# Gate_Driver.net
KiCad netlist of a schematic drawn in Altium Designer
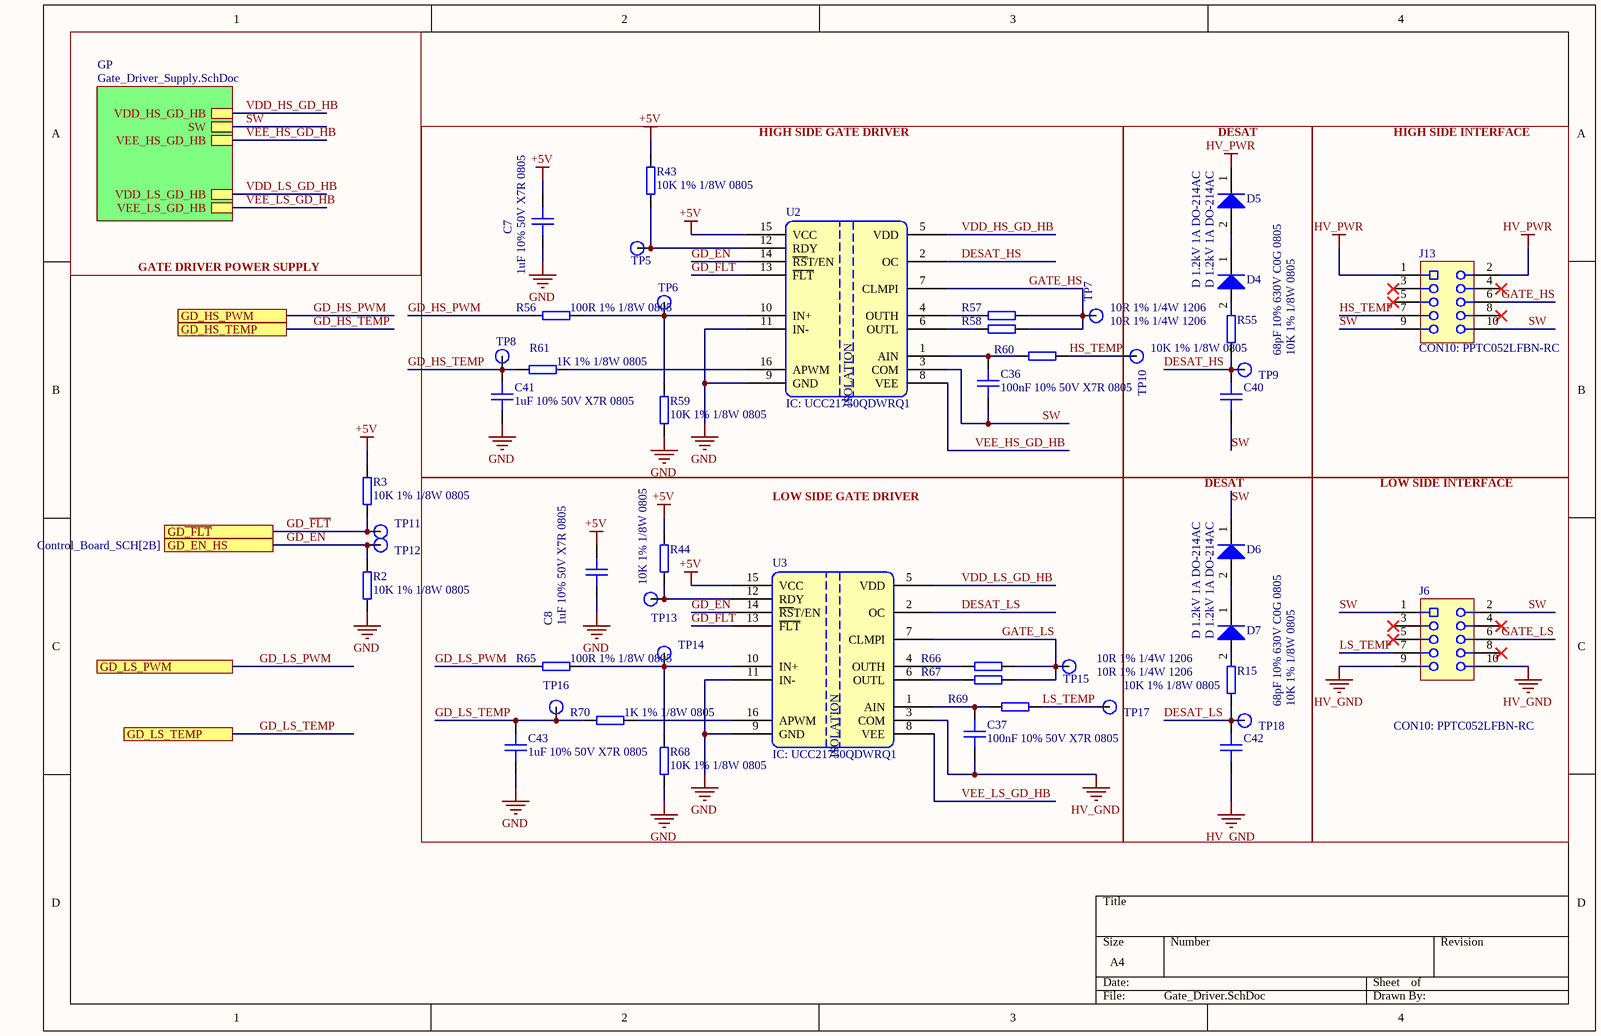
[diagram p0: Gate_Driver.SchDoc]

(export (version "E")
  (design (tool "Eeschema 10.0.6"))
  (components
    (comp (ref "C7")
      (value "1uF 10% 50V X7R 0805")
      (footprint "CAPC2012X10N")
      (fields
        (field (name "MANUFACTURER PART NUMBER") "C2012X7R1H105K125AB")
        (field (name "MANUFACTURER") "TDK")
      )
      (libsource (lib "EMEA- E-Tech Racing- I'Escola d'Enginyeria de Barcelona Est") (part "68pF 10 630V C0G 0805"))
    )
    (comp (ref "C8")
      (value "1uF 10% 50V X7R 0805")
      (footprint "CAPC2012X10N")
      (fields
        (field (name "MANUFACTURER PART NUMBER") "C2012X7R1H105K125AB")
        (field (name "MANUFACTURER") "TDK")
      )
      (libsource (lib "EMEA- E-Tech Racing- I'Escola d'Enginyeria de Barcelona Est") (part "68pF 10 630V C0G 0805"))
    )
    (comp (ref "C36")
      (value "100nF 10% 50V X7R 0805")
      (footprint "CAPC2012X10N")
      (description "Multilayer Ceramic Capacitors MLCC - SMD/SMT 50V 0.1uF X7R 0805 10%")
      (fields
        (field (name "MANUFACTURER") "Stackpole Electronics")
        (field (name "MANUFACTURER PART NUMBER") "CML0805X7R104KT50V")
      )
      (libsource (lib "EMEA- E-Tech Racing- I'Escola d'Enginyeria de Barcelona Est") (part "100nF 10% 50V X7R 0805-Symbol-1"))
    )
    (comp (ref "C37")
      (value "100nF 10% 50V X7R 0805")
      (footprint "CAPC2012X10N")
      (description "Multilayer Ceramic Capacitors MLCC - SMD/SMT 50V 0.1uF X7R 0805 10%")
      (fields
        (field (name "MANUFACTURER") "Stackpole Electronics")
        (field (name "MANUFACTURER PART NUMBER") "CML0805X7R104KT50V")
      )
      (libsource (lib "EMEA- E-Tech Racing- I'Escola d'Enginyeria de Barcelona Est") (part "100nF 10% 50V X7R 0805-Symbol-1"))
    )
    (comp (ref "C40")
      (value "68pF 10% 630V C0G 0805")
      (footprint "CAPC2012X10N")
      (fields
        (field (name "MANUFACTURER") "KEMET")
        (field (name "MANUFACTURER PART NUMBER") "C0805C680JBGACTU")
        (field (name "TOLERANCE") "5%")
      )
      (libsource (lib "EMEA- E-Tech Racing- I'Escola d'Enginyeria de Barcelona Est") (part "68pF 10 630V C0G 0805"))
    )
    (comp (ref "C41")
      (value "1uF 10% 50V X7R 0805")
      (footprint "CAPC2012X10N")
      (fields
        (field (name "MANUFACTURER PART NUMBER") "C2012X7R1H105K125AB")
        (field (name "MANUFACTURER") "TDK")
      )
      (libsource (lib "EMEA- E-Tech Racing- I'Escola d'Enginyeria de Barcelona Est") (part "68pF 10 630V C0G 0805"))
    )
    (comp (ref "C42")
      (value "68pF 10% 630V C0G 0805")
      (footprint "CAPC2012X10N")
      (fields
        (field (name "MANUFACTURER") "KEMET")
        (field (name "MANUFACTURER PART NUMBER") "C0805C680JBGACTU")
        (field (name "TOLERANCE") "5%")
      )
      (libsource (lib "EMEA- E-Tech Racing- I'Escola d'Enginyeria de Barcelona Est") (part "68pF 10 630V C0G 0805"))
    )
    (comp (ref "C43")
      (value "1uF 10% 50V X7R 0805")
      (footprint "CAPC2012X10N")
      (fields
        (field (name "MANUFACTURER PART NUMBER") "C2012X7R1H105K125AB")
        (field (name "MANUFACTURER") "TDK")
      )
      (libsource (lib "EMEA- E-Tech Racing- I'Escola d'Enginyeria de Barcelona Est") (part "68pF 10 630V C0G 0805"))
    )
    (comp (ref "D4")
      (value "D 1.2kV 1A DO-214AC")
      (footprint "FP-95400-MFG")
      (description "Rectifier Diode, 1 Phase, 1 Element, 1A, 1000V V(RRM), Silicon, DO-214AC")
      (fields (field (name "VOLTAGE") "1kV") (field (name "MANUFACTURER") "Vishay"))
      (libsource (lib "EMEA- E-Tech Racing- I'Escola d'Enginyeria de Barcelona Est") (part "SD 1.2kV 1A"))
    )
    (comp (ref "D5")
      (value "D 1.2kV 1A DO-214AC")
      (footprint "FP-95400-MFG")
      (description "Rectifier Diode, 1 Phase, 1 Element, 1A, 1000V V(RRM), Silicon, DO-214AC")
      (fields (field (name "VOLTAGE") "1kV") (field (name "MANUFACTURER") "Vishay"))
      (libsource (lib "EMEA- E-Tech Racing- I'Escola d'Enginyeria de Barcelona Est") (part "SD 1.2kV 1A"))
    )
    (comp (ref "D6")
      (value "D 1.2kV 1A DO-214AC")
      (footprint "FP-95400-MFG")
      (description "Rectifier Diode, 1 Phase, 1 Element, 1A, 1000V V(RRM), Silicon, DO-214AC")
      (fields (field (name "VOLTAGE") "1kV") (field (name "MANUFACTURER") "Vishay"))
      (libsource (lib "EMEA- E-Tech Racing- I'Escola d'Enginyeria de Barcelona Est") (part "SD 1.2kV 1A"))
    )
    (comp (ref "D7")
      (value "D 1.2kV 1A DO-214AC")
      (footprint "FP-95400-MFG")
      (description "Rectifier Diode, 1 Phase, 1 Element, 1A, 1000V V(RRM), Silicon, DO-214AC")
      (fields (field (name "VOLTAGE") "1kV") (field (name "MANUFACTURER") "Vishay"))
      (libsource (lib "EMEA- E-Tech Racing- I'Escola d'Enginyeria de Barcelona Est") (part "SD 1.2kV 1A"))
    )
    (comp (ref "J6")
      (value "CON10: PPTC052LFBN-RC")
      (footprint "SLIN-PPTC052LFBN-RC_V")
      (description "Female, 10C, Straight, .100\"CC; 3.20mm Tail, No Mt. 100u\" Tin; PBT, Phos Bronze, 105 C")
      (fields
        (field (name "MANUFACTURER") "Sullins")
        (field (name "MANUFACTURER PART NUMBER") "PPTC052LFBN-RC")
      )
      (libsource (lib "EMEA- E-Tech Racing- I'Escola d'Enginyeria de Barcelona Est") (part "CN-2P-F-R10"))
    )
    (comp (ref "J13")
      (value "CON10: PPTC052LFBN-RC")
      (footprint "SLIN-PPTC052LFBN-RC_V")
      (description "Female, 10C, Straight, .100\"CC; 3.20mm Tail, No Mt. 100u\" Tin; PBT, Phos Bronze, 105 C")
      (fields
        (field (name "MANUFACTURER") "Sullins")
        (field (name "MANUFACTURER PART NUMBER") "PPTC052LFBN-RC")
      )
      (libsource (lib "EMEA- E-Tech Racing- I'Escola d'Enginyeria de Barcelona Est") (part "CN-2P-F-R10"))
    )
    (comp (ref "R2")
      (value "10K 1% 1/8W 0805")
      (footprint "RESC2012X05N")
      (description "Res Thick Film 0805 10K Ohm 1% 0.125W ±100ppm/°C Molded SMD Paper T/R")
      (fields
        (field (name "MANUFACTURER PART NUMBER") "RMCF0805FT10K0")
        (field (name "MANUFACTURER") "Stackpole Electronics")
      )
      (libsource (lib "EMEA- E-Tech Racing- I'Escola d'Enginyeria de Barcelona Est") (part "100R 1 1/8W 0805"))
    )
    (comp (ref "R3")
      (value "10K 1% 1/8W 0805")
      (footprint "RESC2012X05N")
      (description "Res Thick Film 0805 10K Ohm 1% 0.125W ±100ppm/°C Molded SMD Paper T/R")
      (fields
        (field (name "MANUFACTURER PART NUMBER") "RMCF0805FT10K0")
        (field (name "MANUFACTURER") "Stackpole Electronics")
      )
      (libsource (lib "EMEA- E-Tech Racing- I'Escola d'Enginyeria de Barcelona Est") (part "100R 1 1/8W 0805"))
    )
    (comp (ref "R15")
      (value "10K 1% 1/8W 0805")
      (footprint "RESC2012X05N")
      (description "Res Thick Film 0805 10K Ohm 1% 0.125W ±100ppm/°C Molded SMD Paper T/R")
      (fields (field (name "TOLERANCE") "1%") (field (name "MANUFACTURER PART NUMBER") "RMCF0805FT10K0"))
      (libsource (lib "EMEA- E-Tech Racing- I'Escola d'Enginyeria de Barcelona Est") (part "100R 1 1/8W 0805"))
    )
    (comp (ref "R43")
      (value "10K 1% 1/8W 0805")
      (footprint "RESC2012X05N")
      (description "Res Thick Film 0805 10K Ohm 1% 0.125W ±100ppm/°C Molded SMD Paper T/R")
      (fields
        (field (name "MANUFACTURER PART NUMBER") "RMCF0805FT10K0")
        (field (name "MANUFACTURER") "Stackpole Electronics")
      )
      (libsource (lib "EMEA- E-Tech Racing- I'Escola d'Enginyeria de Barcelona Est") (part "100R 1 1/8W 0805"))
    )
    (comp (ref "R44")
      (value "10K 1% 1/8W 0805")
      (footprint "RESC2012X05N")
      (description "Res Thick Film 0805 10K Ohm 1% 0.125W ±100ppm/°C Molded SMD Paper T/R")
      (fields
        (field (name "MANUFACTURER PART NUMBER") "RMCF0805FT10K0")
        (field (name "MANUFACTURER") "Stackpole Electronics")
      )
      (libsource (lib "EMEA- E-Tech Racing- I'Escola d'Enginyeria de Barcelona Est") (part "100R 1 1/8W 0805"))
    )
    (comp (ref "R55")
      (value "10K 1% 1/8W 0805")
      (footprint "RESC2012X05N")
      (description "Res Thick Film 0805 10K Ohm 1% 0.125W ±100ppm/°C Molded SMD Paper T/R")
      (fields (field (name "TOLERANCE") "1%") (field (name "MANUFACTURER PART NUMBER") "RMCF0805FT10K0"))
      (libsource (lib "EMEA- E-Tech Racing- I'Escola d'Enginyeria de Barcelona Est") (part "100R 1 1/8W 0805"))
    )
    (comp (ref "R56")
      (value "100R 1% 1/8W 0805")
      (footprint "RESC2012X05N")
      (description "Res Thick Film 0805 100 Ohm 1% 0.125W ±100ppm/°C Molded SMD Paper T/R")
      (fields (field (name "TOLERANCE") "1%") (field (name "MANUFACTURER PART NUMBER") "RMCF0805FT100R"))
      (libsource (lib "EMEA- E-Tech Racing- I'Escola d'Enginyeria de Barcelona Est") (part "100R 1 1/8W 0805"))
    )
    (comp (ref "R57")
      (value "10R 1% 1/4W 1206")
      (footprint "RESC3116X06N")
      (description "Res Thick Film 1206 10 Ohm 1% 0.25W(1/4W) ±100ppm/C Pad SMD T/R Automotive AEC-Q200")
      (fields (field (name "MANUFACTURER PART NUMBER") "RMCF1206FT10R0") (field (name "TOLERANCE") "1%"))
      (libsource (lib "EMEA- E-Tech Racing- I'Escola d'Enginyeria de Barcelona Est") (part "100R 1 1/8W 0805"))
    )
    (comp (ref "R58")
      (value "10R 1% 1/4W 1206")
      (footprint "RESC3116X06N")
      (description "Res Thick Film 1206 10 Ohm 1% 0.25W(1/4W) ±100ppm/C Pad SMD T/R Automotive AEC-Q200")
      (fields (field (name "MANUFACTURER PART NUMBER") "RMCF1206FT10R0") (field (name "TOLERANCE") "1%"))
      (libsource (lib "EMEA- E-Tech Racing- I'Escola d'Enginyeria de Barcelona Est") (part "100R 1 1/8W 0805"))
    )
    (comp (ref "R59")
      (value "10K 1% 1/8W 0805")
      (footprint "RESC2012X05N")
      (description "Res Thick Film 0805 10K Ohm 1% 0.125W ±100ppm/°C Molded SMD Paper T/R")
      (fields
        (field (name "MANUFACTURER PART NUMBER") "RMCF0805FT10K0")
        (field (name "MANUFACTURER") "Stackpole Electronics")
      )
      (libsource (lib "EMEA- E-Tech Racing- I'Escola d'Enginyeria de Barcelona Est") (part "100R 1 1/8W 0805"))
    )
    (comp (ref "R60")
      (value "10K 1% 1/8W 0805")
      (footprint "RESC2012X05N")
      (description "Res Thick Film 0805 10K Ohm 1% 0.125W ±100ppm/°C Molded SMD Paper T/R")
      (fields (field (name "TOLERANCE") "1%") (field (name "MANUFACTURER PART NUMBER") "RMCF0805FT10K0"))
      (libsource (lib "EMEA- E-Tech Racing- I'Escola d'Enginyeria de Barcelona Est") (part "100R 1 1/8W 0805"))
    )
    (comp (ref "R61")
      (value "1K 1% 1/8W 0805")
      (footprint "RESC2012X05N")
      (description "Res Thick Film 0805 1K Ohm 1% 0.125W ±100ppm/°C Molded SMD Paper T/R")
      (fields (field (name "TOLERANCE") "1%") (field (name "MANUFACTURER") "Stackpole Electronics"))
      (libsource (lib "EMEA- E-Tech Racing- I'Escola d'Enginyeria de Barcelona Est") (part "100R 1 1/8W 0805"))
    )
    (comp (ref "R65")
      (value "100R 1% 1/8W 0805")
      (footprint "RESC2012X05N")
      (description "Res Thick Film 0805 100 Ohm 1% 0.125W ±100ppm/°C Molded SMD Paper T/R")
      (fields (field (name "TOLERANCE") "1%") (field (name "MANUFACTURER PART NUMBER") "RMCF0805FT100R"))
      (libsource (lib "EMEA- E-Tech Racing- I'Escola d'Enginyeria de Barcelona Est") (part "100R 1 1/8W 0805"))
    )
    (comp (ref "R66")
      (value "10R 1% 1/4W 1206")
      (footprint "RESC3116X06N")
      (description "Res Thick Film 1206 10 Ohm 1% 0.25W(1/4W) ±100ppm/C Pad SMD T/R Automotive AEC-Q200")
      (fields (field (name "MANUFACTURER PART NUMBER") "RMCF1206FT10R0") (field (name "TOLERANCE") "1%"))
      (libsource (lib "EMEA- E-Tech Racing- I'Escola d'Enginyeria de Barcelona Est") (part "100R 1 1/8W 0805"))
    )
    (comp (ref "R67")
      (value "10R 1% 1/4W 1206")
      (footprint "RESC3116X06N")
      (description "Res Thick Film 1206 10 Ohm 1% 0.25W(1/4W) ±100ppm/C Pad SMD T/R Automotive AEC-Q200")
      (fields (field (name "MANUFACTURER PART NUMBER") "RMCF1206FT10R0") (field (name "TOLERANCE") "1%"))
      (libsource (lib "EMEA- E-Tech Racing- I'Escola d'Enginyeria de Barcelona Est") (part "100R 1 1/8W 0805"))
    )
    (comp (ref "R68")
      (value "10K 1% 1/8W 0805")
      (footprint "RESC2012X05N")
      (description "Res Thick Film 0805 10K Ohm 1% 0.125W ±100ppm/°C Molded SMD Paper T/R")
      (fields
        (field (name "MANUFACTURER PART NUMBER") "RMCF0805FT10K0")
        (field (name "MANUFACTURER") "Stackpole Electronics")
      )
      (libsource (lib "EMEA- E-Tech Racing- I'Escola d'Enginyeria de Barcelona Est") (part "100R 1 1/8W 0805"))
    )
    (comp (ref "R69")
      (value "10K 1% 1/8W 0805")
      (footprint "RESC2012X05N")
      (description "Res Thick Film 0805 10K Ohm 1% 0.125W ±100ppm/°C Molded SMD Paper T/R")
      (fields (field (name "TOLERANCE") "1%") (field (name "MANUFACTURER PART NUMBER") "RMCF0805FT10K0"))
      (libsource (lib "EMEA- E-Tech Racing- I'Escola d'Enginyeria de Barcelona Est") (part "100R 1 1/8W 0805"))
    )
    (comp (ref "R70")
      (value "1K 1% 1/8W 0805")
      (footprint "RESC2012X05N")
      (description "Res Thick Film 0805 1K Ohm 1% 0.125W ±100ppm/°C Molded SMD Paper T/R")
      (fields (field (name "TOLERANCE") "1%") (field (name "MANUFACTURER") "Stackpole Electronics"))
      (libsource (lib "EMEA- E-Tech Racing- I'Escola d'Enginyeria de Barcelona Est") (part "100R 1 1/8W 0805"))
    )
    (comp (ref "TP5")
      (value "TestPoint")
      (footprint "Test Point-Footprint-1")
      (libsource (lib "EMEA- E-Tech Racing- I'Escola d'Enginyeria de Barcelona Est") (part "New symbol 1"))
    )
    (comp (ref "TP6")
      (value "TestPoint")
      (footprint "Test Point-Footprint-1")
      (libsource (lib "EMEA- E-Tech Racing- I'Escola d'Enginyeria de Barcelona Est") (part "New symbol 1"))
    )
    (comp (ref "TP7")
      (value "TestPoint")
      (footprint "Test Point-Footprint-1")
      (libsource (lib "EMEA- E-Tech Racing- I'Escola d'Enginyeria de Barcelona Est") (part "New symbol 1"))
    )
    (comp (ref "TP8")
      (value "TestPoint")
      (footprint "Test Point-Footprint-1")
      (libsource (lib "EMEA- E-Tech Racing- I'Escola d'Enginyeria de Barcelona Est") (part "New symbol 1"))
    )
    (comp (ref "TP9")
      (value "TestPoint")
      (footprint "Test Point-Footprint-1")
      (libsource (lib "EMEA- E-Tech Racing- I'Escola d'Enginyeria de Barcelona Est") (part "New symbol 1"))
    )
    (comp (ref "TP10")
      (value "TestPoint")
      (footprint "Test Point-Footprint-1")
      (libsource (lib "EMEA- E-Tech Racing- I'Escola d'Enginyeria de Barcelona Est") (part "New symbol 1"))
    )
    (comp (ref "TP11")
      (value "TestPoint")
      (footprint "Test Point-Footprint-1")
      (libsource (lib "EMEA- E-Tech Racing- I'Escola d'Enginyeria de Barcelona Est") (part "New symbol 1"))
    )
    (comp (ref "TP12")
      (value "TestPoint")
      (footprint "Test Point-Footprint-1")
      (libsource (lib "EMEA- E-Tech Racing- I'Escola d'Enginyeria de Barcelona Est") (part "New symbol 1"))
    )
    (comp (ref "TP13")
      (value "TestPoint")
      (footprint "Test Point-Footprint-1")
      (libsource (lib "EMEA- E-Tech Racing- I'Escola d'Enginyeria de Barcelona Est") (part "New symbol 1"))
    )
    (comp (ref "TP14")
      (value "TestPoint")
      (footprint "Test Point-Footprint-1")
      (libsource (lib "EMEA- E-Tech Racing- I'Escola d'Enginyeria de Barcelona Est") (part "New symbol 1"))
    )
    (comp (ref "TP15")
      (value "TestPoint")
      (footprint "Test Point-Footprint-1")
      (libsource (lib "EMEA- E-Tech Racing- I'Escola d'Enginyeria de Barcelona Est") (part "New symbol 1"))
    )
    (comp (ref "TP16")
      (value "TestPoint")
      (footprint "Test Point-Footprint-1")
      (libsource (lib "EMEA- E-Tech Racing- I'Escola d'Enginyeria de Barcelona Est") (part "New symbol 1"))
    )
    (comp (ref "TP17")
      (value "TestPoint")
      (footprint "Test Point-Footprint-1")
      (libsource (lib "EMEA- E-Tech Racing- I'Escola d'Enginyeria de Barcelona Est") (part "New symbol 1"))
    )
    (comp (ref "TP18")
      (value "TestPoint")
      (footprint "Test Point-Footprint-1")
      (libsource (lib "EMEA- E-Tech Racing- I'Escola d'Enginyeria de Barcelona Est") (part "New symbol 1"))
    )
    (comp (ref "U2")
      (value "IC: UCC21750QDWRQ1")
      (footprint "SOIC127P1030X265-16N")
      (description "Gate Driver Reinforced Isolated Single Channel 10A 5.7kV 16-Pin SOIC T/R Automotive")
      (fields
        (field (name "MANUFACTURER PART NUMBER") "UCC21750QDWRQ1")
        (field (name "MANUFACTURER") "Texas Instruments")
      )
      (libsource (lib "EMEA- E-Tech Racing- I'Escola d'Enginyeria de Barcelona Est") (part "IC{colon} UCC21710QDWRQ1"))
    )
    (comp (ref "U3")
      (value "IC: UCC21750QDWRQ1")
      (footprint "SOIC127P1030X265-16N")
      (description "Gate Driver Reinforced Isolated Single Channel 10A 5.7kV 16-Pin SOIC T/R Automotive")
      (fields
        (field (name "MANUFACTURER PART NUMBER") "UCC21750QDWRQ1")
        (field (name "MANUFACTURER") "Texas Instruments")
      )
      (libsource (lib "EMEA- E-Tech Racing- I'Escola d'Enginyeria de Barcelona Est") (part "IC{colon} UCC21710QDWRQ1"))
    )
  )
  (nets
    (net (code "1") (name "+5V") (class "Default")
      (node (ref "C7") (pin "2") (pinfunction "2_2") (pintype "passive"))
      (node (ref "C8") (pin "2") (pinfunction "2_2") (pintype "passive"))
      (node (ref "R3") (pin "2") (pinfunction "2_2") (pintype "passive"))
      (node (ref "R43") (pin "2") (pinfunction "2_2") (pintype "passive"))
      (node (ref "R44") (pin "2") (pinfunction "2_2") (pintype "passive"))
      (node (ref "U2") (pin "15") (pinfunction "VCC_15") (pintype "passive"))
      (node (ref "U3") (pin "15") (pinfunction "VCC_15") (pintype "passive"))
    )
    (net (code "2") (name "/DESAT_HS") (class "Default")
      (node (ref "C40") (pin "2") (pinfunction "2_2") (pintype "passive"))
      (node (ref "R55") (pin "1") (pinfunction "1_1") (pintype "passive"))
      (node (ref "TP9") (pin "1") (pinfunction "1_1") (pintype "passive"))
      (node (ref "U2") (pin "2") (pinfunction "OC_2") (pintype "passive"))
    )
    (net (code "3") (name "/DESAT_LS") (class "Default")
      (node (ref "C42") (pin "2") (pinfunction "2_2") (pintype "passive"))
      (node (ref "R15") (pin "1") (pinfunction "1_1") (pintype "passive"))
      (node (ref "TP18") (pin "1") (pinfunction "1_1") (pintype "passive"))
      (node (ref "U3") (pin "2") (pinfunction "OC_2") (pintype "passive"))
    )
    (net (code "4") (name "/GATE_HS") (class "Default")
      (node (ref "J13") (pin "6") (pinfunction "6_6") (pintype "passive"))
      (node (ref "R57") (pin "2") (pinfunction "2_2") (pintype "passive"))
      (node (ref "R58") (pin "2") (pinfunction "2_2") (pintype "passive"))
      (node (ref "TP7") (pin "1") (pinfunction "1_1") (pintype "passive"))
      (node (ref "U2") (pin "7") (pinfunction "CLMPI_7") (pintype "passive"))
    )
    (net (code "5") (name "/GATE_LS") (class "Default")
      (node (ref "J6") (pin "6") (pinfunction "6_6") (pintype "passive"))
      (node (ref "R66") (pin "2") (pinfunction "2_2") (pintype "passive"))
      (node (ref "R67") (pin "2") (pinfunction "2_2") (pintype "passive"))
      (node (ref "TP15") (pin "1") (pinfunction "1_1") (pintype "passive"))
      (node (ref "U3") (pin "7") (pinfunction "CLMPI_7") (pintype "passive"))
    )
    (net (code "6") (name "/GD_EN") (class "Default")
      (node (ref "R2") (pin "2") (pinfunction "2_2") (pintype "passive"))
      (node (ref "TP12") (pin "1") (pinfunction "1_1") (pintype "passive"))
      (node (ref "U2") (pin "14") (pinfunction "~{RS}T/EN_14") (pintype "passive"))
      (node (ref "U3") (pin "14") (pinfunction "~{RS}T/EN_14") (pintype "passive"))
    )
    (net (code "7") (name "/GD_HS_PWM") (class "Default")
      (node (ref "R56") (pin "1") (pinfunction "1_1") (pintype "passive"))
    )
    (net (code "8") (name "/GD_HS_TEMP") (class "Default")
      (node (ref "C41") (pin "2") (pinfunction "2_2") (pintype "passive"))
      (node (ref "R61") (pin "1") (pinfunction "1_1") (pintype "passive"))
      (node (ref "TP8") (pin "1") (pinfunction "1_1") (pintype "passive"))
    )
    (net (code "9") (name "/GD_LS_PWM") (class "Default")
      (node (ref "R65") (pin "1") (pinfunction "1_1") (pintype "passive"))
    )
    (net (code "10") (name "/GD_LS_TEMP") (class "Default")
      (node (ref "C43") (pin "2") (pinfunction "2_2") (pintype "passive"))
      (node (ref "R70") (pin "1") (pinfunction "1_1") (pintype "passive"))
      (node (ref "TP16") (pin "1") (pinfunction "1_1") (pintype "passive"))
    )
    (net (code "11") (name "/GD_~{FLT}") (class "Default")
      (node (ref "R3") (pin "1") (pinfunction "1_1") (pintype "passive"))
      (node (ref "TP11") (pin "1") (pinfunction "1_1") (pintype "passive"))
      (node (ref "U2") (pin "13") (pinfunction "~{FLT}_13") (pintype "passive"))
      (node (ref "U3") (pin "13") (pinfunction "~{FLT}_13") (pintype "passive"))
    )
    (net (code "12") (name "/HS_TEMP") (class "Default")
      (node (ref "J13") (pin "7") (pinfunction "7_7") (pintype "passive"))
      (node (ref "R60") (pin "2") (pinfunction "2_2") (pintype "passive"))
      (node (ref "TP10") (pin "1") (pinfunction "1_1") (pintype "passive"))
    )
    (net (code "13") (name "/LS_TEMP") (class "Default")
      (node (ref "J6") (pin "7") (pinfunction "7_7") (pintype "passive"))
      (node (ref "R69") (pin "2") (pinfunction "2_2") (pintype "passive"))
      (node (ref "TP17") (pin "1") (pinfunction "1_1") (pintype "passive"))
    )
    (net (code "14") (name "/SW") (class "Default")
      (node (ref "C36") (pin "2") (pinfunction "2_2") (pintype "passive"))
      (node (ref "C40") (pin "1") (pinfunction "1_1") (pintype "passive"))
      (node (ref "D6") (pin "1") (pinfunction "K_1") (pintype "passive"))
      (node (ref "J13") (pin "10") (pinfunction "10_10") (pintype "passive"))
      (node (ref "J13") (pin "9") (pinfunction "9_9") (pintype "passive"))
      (node (ref "J6") (pin "1") (pinfunction "1_1") (pintype "passive"))
      (node (ref "J6") (pin "2") (pinfunction "2_2") (pintype "passive"))
      (node (ref "U2") (pin "3") (pinfunction "COM_3") (pintype "passive"))
    )
    (net (code "15") (name "/VDD_HS_GD_HB") (class "Default")
      (node (ref "U2") (pin "5") (pinfunction "VDD_5") (pintype "passive"))
    )
    (net (code "16") (name "/VDD_LS_GD_HB") (class "Default")
      (node (ref "U3") (pin "5") (pinfunction "VDD_5") (pintype "passive"))
    )
    (net (code "17") (name "/VEE_HS_GD_HB") (class "Default")
      (node (ref "U2") (pin "8") (pinfunction "VEE_8") (pintype "passive"))
    )
    (net (code "18") (name "/VEE_LS_GD_HB") (class "Default")
      (node (ref "U3") (pin "8") (pinfunction "VEE_8") (pintype "passive"))
    )
    (net (code "19") (name "GND") (class "Default")
      (node (ref "C41") (pin "1") (pinfunction "1_1") (pintype "passive"))
      (node (ref "C43") (pin "1") (pinfunction "1_1") (pintype "passive"))
      (node (ref "C7") (pin "1") (pinfunction "1_1") (pintype "passive"))
      (node (ref "C8") (pin "1") (pinfunction "1_1") (pintype "passive"))
      (node (ref "R2") (pin "1") (pinfunction "1_1") (pintype "passive"))
      (node (ref "R59") (pin "1") (pinfunction "1_1") (pintype "passive"))
      (node (ref "R68") (pin "1") (pinfunction "1_1") (pintype "passive"))
      (node (ref "U2") (pin "11") (pinfunction "IN-_11") (pintype "passive"))
      (node (ref "U2") (pin "9") (pinfunction "GND_9") (pintype "passive"))
      (node (ref "U3") (pin "11") (pinfunction "IN-_11") (pintype "passive"))
      (node (ref "U3") (pin "9") (pinfunction "GND_9") (pintype "passive"))
    )
    (net (code "20") (name "HV_GND") (class "Default")
      (node (ref "C37") (pin "2") (pinfunction "2_2") (pintype "passive"))
      (node (ref "C42") (pin "1") (pinfunction "1_1") (pintype "passive"))
      (node (ref "J6") (pin "10") (pinfunction "10_10") (pintype "passive"))
      (node (ref "J6") (pin "9") (pinfunction "9_9") (pintype "passive"))
      (node (ref "U3") (pin "3") (pinfunction "COM_3") (pintype "passive"))
    )
    (net (code "21") (name "HV_PWR") (class "Default")
      (node (ref "D5") (pin "1") (pinfunction "K_1") (pintype "passive"))
      (node (ref "J13") (pin "1") (pinfunction "1_1") (pintype "passive"))
      (node (ref "J13") (pin "2") (pinfunction "2_2") (pintype "passive"))
    )
    (net (code "22") (name "Net-(D4-A)") (class "Default")
      (node (ref "D4") (pin "2") (pinfunction "A_2") (pintype "passive"))
      (node (ref "R55") (pin "2") (pinfunction "2_2") (pintype "passive"))
    )
    (net (code "23") (name "Net-(D4-K)") (class "Default")
      (node (ref "D4") (pin "1") (pinfunction "K_1") (pintype "passive"))
      (node (ref "D5") (pin "2") (pinfunction "A_2") (pintype "passive"))
    )
    (net (code "24") (name "Net-(D6-A)") (class "Default")
      (node (ref "D6") (pin "2") (pinfunction "A_2") (pintype "passive"))
      (node (ref "D7") (pin "1") (pinfunction "K_1") (pintype "passive"))
    )
    (net (code "25") (name "Net-(D7-A)") (class "Default")
      (node (ref "D7") (pin "2") (pinfunction "A_2") (pintype "passive"))
      (node (ref "R15") (pin "2") (pinfunction "2_2") (pintype "passive"))
    )
    (net (code "26") (name "Net-(U2-AIN)") (class "Default")
      (node (ref "C36") (pin "1") (pinfunction "1_1") (pintype "passive"))
      (node (ref "R60") (pin "1") (pinfunction "1_1") (pintype "passive"))
      (node (ref "U2") (pin "1") (pinfunction "AIN_1") (pintype "passive"))
    )
    (net (code "27") (name "Net-(U2-APWM)") (class "Default")
      (node (ref "R61") (pin "2") (pinfunction "2_2") (pintype "passive"))
      (node (ref "U2") (pin "16") (pinfunction "APWM_16") (pintype "passive"))
    )
    (net (code "28") (name "Net-(U2-IN+)") (class "Default")
      (node (ref "R56") (pin "2") (pinfunction "2_2") (pintype "passive"))
      (node (ref "R59") (pin "2") (pinfunction "2_2") (pintype "passive"))
      (node (ref "TP6") (pin "1") (pinfunction "1_1") (pintype "passive"))
      (node (ref "U2") (pin "10") (pinfunction "IN+_10") (pintype "passive"))
    )
    (net (code "29") (name "Net-(U2-OUTH)") (class "Default")
      (node (ref "R57") (pin "1") (pinfunction "1_1") (pintype "passive"))
      (node (ref "U2") (pin "4") (pinfunction "OUTH_4") (pintype "passive"))
    )
    (net (code "30") (name "Net-(U2-OUTL)") (class "Default")
      (node (ref "R58") (pin "1") (pinfunction "1_1") (pintype "passive"))
      (node (ref "U2") (pin "6") (pinfunction "OUTL_6") (pintype "passive"))
    )
    (net (code "31") (name "Net-(U2-RDY)") (class "Default")
      (node (ref "R43") (pin "1") (pinfunction "1_1") (pintype "passive"))
      (node (ref "TP5") (pin "1") (pinfunction "1_1") (pintype "passive"))
      (node (ref "U2") (pin "12") (pinfunction "RDY_12") (pintype "passive"))
    )
    (net (code "32") (name "Net-(U3-AIN)") (class "Default")
      (node (ref "C37") (pin "1") (pinfunction "1_1") (pintype "passive"))
      (node (ref "R69") (pin "1") (pinfunction "1_1") (pintype "passive"))
      (node (ref "U3") (pin "1") (pinfunction "AIN_1") (pintype "passive"))
    )
    (net (code "33") (name "Net-(U3-APWM)") (class "Default")
      (node (ref "R70") (pin "2") (pinfunction "2_2") (pintype "passive"))
      (node (ref "U3") (pin "16") (pinfunction "APWM_16") (pintype "passive"))
    )
    (net (code "34") (name "Net-(U3-IN+)") (class "Default")
      (node (ref "R65") (pin "2") (pinfunction "2_2") (pintype "passive"))
      (node (ref "R68") (pin "2") (pinfunction "2_2") (pintype "passive"))
      (node (ref "TP14") (pin "1") (pinfunction "1_1") (pintype "passive"))
      (node (ref "U3") (pin "10") (pinfunction "IN+_10") (pintype "passive"))
    )
    (net (code "35") (name "Net-(U3-OUTH)") (class "Default")
      (node (ref "R66") (pin "1") (pinfunction "1_1") (pintype "passive"))
      (node (ref "U3") (pin "4") (pinfunction "OUTH_4") (pintype "passive"))
    )
    (net (code "36") (name "Net-(U3-OUTL)") (class "Default")
      (node (ref "R67") (pin "1") (pinfunction "1_1") (pintype "passive"))
      (node (ref "U3") (pin "6") (pinfunction "OUTL_6") (pintype "passive"))
    )
    (net (code "37") (name "Net-(U3-RDY)") (class "Default")
      (node (ref "R44") (pin "1") (pinfunction "1_1") (pintype "passive"))
      (node (ref "TP13") (pin "1") (pinfunction "1_1") (pintype "passive"))
      (node (ref "U3") (pin "12") (pinfunction "RDY_12") (pintype "passive"))
    )
    (net (code "38") (name "unconnected-(J6-Pad3)") (class "Default")
      (node (ref "J6") (pin "3") (pinfunction "3_3") (pintype "passive+no_connect"))
    )
    (net (code "39") (name "unconnected-(J6-Pad4)") (class "Default")
      (node (ref "J6") (pin "4") (pinfunction "4_4") (pintype "passive+no_connect"))
    )
    (net (code "40") (name "unconnected-(J6-Pad5)") (class "Default")
      (node (ref "J6") (pin "5") (pinfunction "5_5") (pintype "passive+no_connect"))
    )
    (net (code "41") (name "unconnected-(J6-Pad8)") (class "Default")
      (node (ref "J6") (pin "8") (pinfunction "8_8") (pintype "passive+no_connect"))
    )
    (net (code "42") (name "unconnected-(J13-Pad3)") (class "Default")
      (node (ref "J13") (pin "3") (pinfunction "3_3") (pintype "passive+no_connect"))
    )
    (net (code "43") (name "unconnected-(J13-Pad4)") (class "Default")
      (node (ref "J13") (pin "4") (pinfunction "4_4") (pintype "passive+no_connect"))
    )
    (net (code "44") (name "unconnected-(J13-Pad5)") (class "Default")
      (node (ref "J13") (pin "5") (pinfunction "5_5") (pintype "passive+no_connect"))
    )
    (net (code "45") (name "unconnected-(J13-Pad8)") (class "Default")
      (node (ref "J13") (pin "8") (pinfunction "8_8") (pintype "passive+no_connect"))
    )
  )
)
